# OneChip.net
KiCad netlist of a schematic drawn in Altium Designer
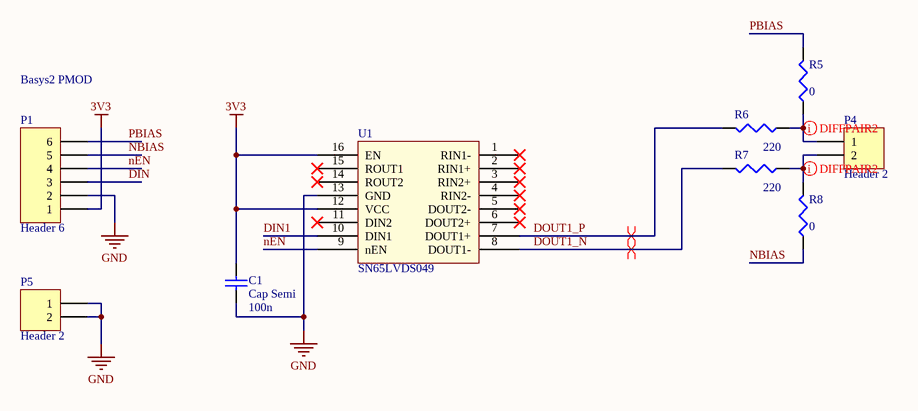
[diagram p0: OneChip.SchDoc]

(export (version "E")
  (design (tool "Eeschema 10.0.6"))
  (components
    (comp (ref "C1")
      (value "Cap Semi")
      (footprint "1608[0603]")
      (description "Capacitor (Semiconductor SIM Model)")
      (fields (field (name "ALTIUM_VALUE") "100n") (field (name "PUBLISHER") "Altium Limited"))
      (libsource (lib "Miscellaneous Devices") (part "Cap Semi"))
    )
    (comp (ref "P1")
      (value "Header 6")
      (footprint "HDR1X6")
      (description "Header, 6-Pin")
      (fields (field (name "PUBLISHER") "Altium Limited"))
      (libsource (lib "Miscellaneous Connectors") (part "Header 6"))
    )
    (comp (ref "P4")
      (value "Header 2")
      (footprint "HDR1X2")
      (description "Header, 2-Pin")
      (fields (field (name "PUBLISHER") "Altium Limited"))
      (libsource (lib "") (part "Header 2_1"))
    )
    (comp (ref "P5")
      (value "Header 2")
      (footprint "HDR1X2")
      (description "Header, 2-Pin")
      (fields (field (name "PUBLISHER") "Altium Limited"))
      (libsource (lib "Miscellaneous Connectors") (part "Header 2"))
    )
    (comp (ref "R5")
      (value "0")
      (footprint "J1-0603")
      (description "Resistor")
      (fields (field (name "Comment") "Res3") (field (name "PUBLISHER") "Altium Limited"))
      (libsource (lib "Miscellaneous Devices") (part "Res3"))
    )
    (comp (ref "R6")
      (value "220")
      (footprint "J1-0603")
      (description "Resistor")
      (fields (field (name "Comment") "Res3") (field (name "PUBLISHER") "Altium Limited"))
      (libsource (lib "Miscellaneous Devices") (part "Res3"))
    )
    (comp (ref "R7")
      (value "220")
      (footprint "J1-0603")
      (description "Resistor")
      (fields (field (name "Comment") "Res3") (field (name "PUBLISHER") "Altium Limited"))
      (libsource (lib "Miscellaneous Devices") (part "Res3"))
    )
    (comp (ref "R8")
      (value "0")
      (footprint "J1-0603")
      (description "Resistor")
      (fields (field (name "Comment") "Res3") (field (name "PUBLISHER") "Altium Limited"))
      (libsource (lib "Miscellaneous Devices") (part "Res3"))
    )
    (comp (ref "U1")
      (value "SN65LVDS049")
      (footprint "SOP127P600-8N")
      (libsource (lib "Schlib1") (part "SN65LVDS049"))
    )
  )
  (nets
    (net (code "1") (name "/DIN") (class "Default")
      (node (ref "P1") (pin "3") (pinfunction "3_3") (pintype "passive"))
    )
    (net (code "2") (name "/DIN1") (class "Default")
      (node (ref "U1") (pin "10") (pinfunction "DIN1_10") (pintype "passive"))
    )
    (net (code "3") (name "/DOUT1_N") (class "Default")
      (node (ref "R7") (pin "2") (pinfunction "2_2") (pintype "passive"))
      (node (ref "U1") (pin "8") (pinfunction "DOUT1-_8") (pintype "passive"))
    )
    (net (code "4") (name "/DOUT1_P") (class "Default")
      (node (ref "R6") (pin "2") (pinfunction "2_2") (pintype "passive"))
      (node (ref "U1") (pin "7") (pinfunction "DOUT1+_7") (pintype "passive"))
    )
    (net (code "5") (name "/NBIAS") (class "Default")
      (node (ref "P1") (pin "5") (pinfunction "5_5") (pintype "passive"))
      (node (ref "R8") (pin "1") (pinfunction "1_1") (pintype "passive"))
    )
    (net (code "6") (name "/PBIAS") (class "Default")
      (node (ref "P1") (pin "6") (pinfunction "6_6") (pintype "passive"))
      (node (ref "R5") (pin "2") (pinfunction "2_2") (pintype "passive"))
    )
    (net (code "7") (name "/nEN") (class "Default")
      (node (ref "P1") (pin "4") (pinfunction "4_4") (pintype "passive"))
      (node (ref "U1") (pin "9") (pinfunction "nEN_9") (pintype "passive"))
    )
    (net (code "8") (name "3V3") (class "Default")
      (node (ref "C1") (pin "2") (pinfunction "2_2") (pintype "passive"))
      (node (ref "P1") (pin "1") (pinfunction "1_1") (pintype "passive"))
      (node (ref "U1") (pin "12") (pinfunction "VCC_12") (pintype "passive"))
      (node (ref "U1") (pin "16") (pinfunction "EN_16") (pintype "passive"))
    )
    (net (code "9") (name "GND") (class "Default")
      (node (ref "C1") (pin "1") (pinfunction "1_1") (pintype "passive"))
      (node (ref "P1") (pin "2") (pinfunction "2_2") (pintype "passive"))
      (node (ref "P5") (pin "1") (pinfunction "1_1") (pintype "passive"))
      (node (ref "P5") (pin "2") (pinfunction "2_2") (pintype "passive"))
      (node (ref "U1") (pin "13") (pinfunction "GND_13") (pintype "passive"))
    )
    (net (code "10") (name "Net-(P4-Pad1)") (class "Default")
      (node (ref "P4") (pin "1") (pinfunction "1_1") (pintype "passive"))
      (node (ref "R5") (pin "1") (pinfunction "1_1") (pintype "passive"))
      (node (ref "R6") (pin "1") (pinfunction "1_1") (pintype "passive"))
    )
    (net (code "11") (name "Net-(P4-Pad2)") (class "Default")
      (node (ref "P4") (pin "2") (pinfunction "2_2") (pintype "passive"))
      (node (ref "R7") (pin "1") (pinfunction "1_1") (pintype "passive"))
      (node (ref "R8") (pin "2") (pinfunction "2_2") (pintype "passive"))
    )
    (net (code "12") (name "unconnected-(U1-DIN2-Pad11)") (class "Default")
      (node (ref "U1") (pin "11") (pinfunction "DIN2_11") (pintype "passive+no_connect"))
    )
    (net (code "13") (name "unconnected-(U1-DOUT2+-Pad6)") (class "Default")
      (node (ref "U1") (pin "6") (pinfunction "DOUT2+_6") (pintype "passive+no_connect"))
    )
    (net (code "14") (name "unconnected-(U1-DOUT2--Pad5)") (class "Default")
      (node (ref "U1") (pin "5") (pinfunction "DOUT2-_5") (pintype "passive+no_connect"))
    )
    (net (code "15") (name "unconnected-(U1-RIN1+-Pad2)") (class "Default")
      (node (ref "U1") (pin "2") (pinfunction "RIN1+_2") (pintype "passive+no_connect"))
    )
    (net (code "16") (name "unconnected-(U1-RIN1--Pad1)") (class "Default")
      (node (ref "U1") (pin "1") (pinfunction "RIN1-_1") (pintype "passive+no_connect"))
    )
    (net (code "17") (name "unconnected-(U1-RIN2+-Pad3)") (class "Default")
      (node (ref "U1") (pin "3") (pinfunction "RIN2+_3") (pintype "passive+no_connect"))
    )
    (net (code "18") (name "unconnected-(U1-RIN2--Pad4)") (class "Default")
      (node (ref "U1") (pin "4") (pinfunction "RIN2-_4") (pintype "passive+no_connect"))
    )
    (net (code "19") (name "unconnected-(U1-ROUT1-Pad15)") (class "Default")
      (node (ref "U1") (pin "15") (pinfunction "ROUT1_15") (pintype "passive+no_connect"))
    )
    (net (code "20") (name "unconnected-(U1-ROUT2-Pad14)") (class "Default")
      (node (ref "U1") (pin "14") (pinfunction "ROUT2_14") (pintype "passive+no_connect"))
    )
  )
)
